# OnBoardOsc.net
KiCad netlist of a schematic drawn in Altium Designer
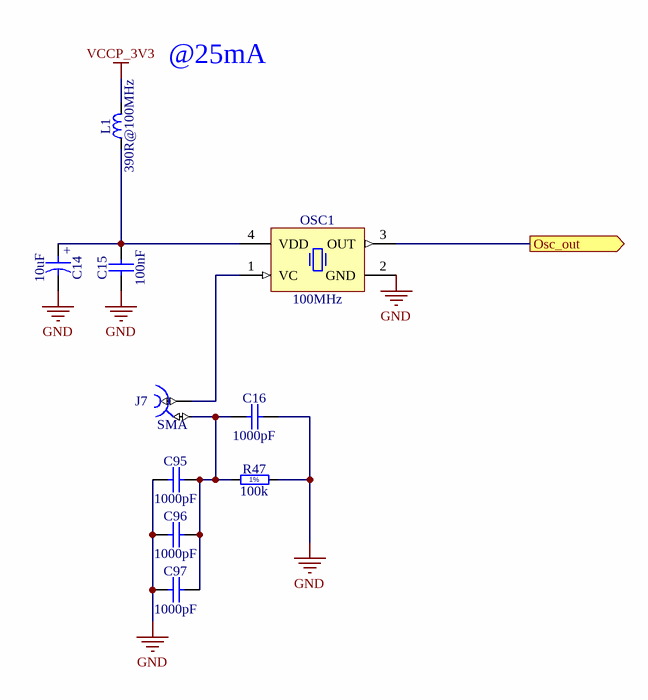
[diagram p0: OnBoardOsc.SchDoc]

(export (version "E")
  (design (tool "Eeschema 10.0.6"))
  (components
    (comp (ref "C14")
      (value "10uF")
      (footprint "CAPMP3216X180N")
      (description "Polarised capacitor")
      (fields
        (field (name "PART NUMBER") "CTE3216-18_10UF_10V_10%_LESR1800")
        (field (name "VOLTAGE") "10V")
        (field (name "AUTHOR") "CERN DEM JLC")
      )
      (libsource (lib "Capacitors") (part "Capacitor - polarized"))
    )
    (comp (ref "C15")
      (value "100nF")
      (footprint "CAPC1005X55N")
      (description "Non-polarised capacitor")
      (fields
        (field (name "PART NUMBER") "CC0402_100NF_16V_10%_X7R")
        (field (name "VOLTAGE") "16V")
        (field (name "AUTHOR") "CERN DEM JLC")
      )
      (libsource (lib "Capacitors") (part "Capacitor - non polarized"))
    )
    (comp (ref "C16")
      (value "1000pF")
      (footprint "CAPC1005X55N")
      (description "Non-polarised capacitor")
      (fields
        (field (name "PART NUMBER") "CC0402_1000PF_50V_5%_C0G")
        (field (name "VOLTAGE") "50V")
        (field (name "AUTHOR") "CERN DEM JLC")
      )
      (libsource (lib "Capacitors") (part "Capacitor - non polarized"))
    )
    (comp (ref "C95")
      (value "1000pF")
      (footprint "CAPC1005X55N")
      (description "Non-polarised capacitor")
      (fields
        (field (name "PART NUMBER") "CC0402_1000PF_50V_5%_C0G")
        (field (name "VOLTAGE") "50V")
        (field (name "AUTHOR") "CERN DEM JLC")
      )
      (libsource (lib "Capacitors") (part "Capacitor - non polarized"))
    )
    (comp (ref "C96")
      (value "1000pF")
      (footprint "CAPC1005X55N")
      (description "Non-polarised capacitor")
      (fields
        (field (name "PART NUMBER") "CC0402_1000PF_50V_5%_C0G")
        (field (name "VOLTAGE") "50V")
        (field (name "AUTHOR") "CERN DEM JLC")
      )
      (libsource (lib "Capacitors") (part "Capacitor - non polarized"))
    )
    (comp (ref "C97")
      (value "1000pF")
      (footprint "CAPC1005X55N")
      (description "Non-polarised capacitor")
      (fields
        (field (name "PART NUMBER") "CC0402_1000PF_50V_5%_C0G")
        (field (name "VOLTAGE") "50V")
        (field (name "AUTHOR") "CERN DEM JLC")
      )
      (libsource (lib "Capacitors") (part "Capacitor - non polarized"))
    )
    (comp (ref "J7")
      (value "SMA")
      (footprint "HUBER-SUHNER_82_SMA-50-0-41/133_NE")
      (fields
        (field (name "PART NUMBER") "HUBER-SUHNER_82_SMA-50-0-41/133_NE")
        (field (name "MANUFACTURER") "HUBER+SUHNER")
        (field (name "MANUFACTURER PART NUMBER") "82_SMA-50-0-41/133_NE")
        (field (name "AUTHOR") "CERN DEM JLC")
      )
      (libsource (lib "Connectors") (part "Coax_1Female_1Shield"))
    )
    (comp (ref "L1")
      (value "390R@100MHz")
      (footprint "INDC1608X95N")
      (description "Inductor")
      (fields
        (field (name "PART NUMBER") "IND0603_TDK_MPZ1608R391A")
        (field (name "POWER") "1.2A")
        (field (name "AUTHOR") "CERN DEM JLC")
      )
      (libsource (lib "Inductors & Transformers") (part "Inductor"))
    )
    (comp (ref "OSC1")
      (value "100MHz")
      (footprint "OSC_CRYSTEK_CVHD-950")
      (description "Oscillator 4 pins 1=VC 2=GND 3=OUT 4=VDD")
      (fields
        (field (name "PART NUMBER") "OSC_100MHZ_CRYSTEK_CVHD-950-100.000")
        (field (name "MANUFACTURER") "CRYSTEK CRYSTAL")
        (field (name "AUTHOR") "CERN DEM BC")
      )
      (libsource (lib "ICs And Semiconductors") (part "Oscillator 1VC 2GND 3OUT 4VDD"))
    )
    (comp (ref "R47")
      (value "100k")
      (footprint "RESC1005X40N")
      (description "Resistor - 1%")
      (fields
        (field (name "PART NUMBER") "R0402_100k_1%_0.0625W_100PPM")
        (field (name "POWER") "0.0625W")
        (field (name "AUTHOR") "CERN DEM JLC")
      )
      (libsource (lib "Resistors") (part "Resistor - 1%"))
    )
  )
  (nets
    (net (code "1") (name "/Osc_out") (class "Default")
      (node (ref "OSC1") (pin "3") (pinfunction "OUT_3") (pintype "output"))
    )
    (net (code "2") (name "GND") (class "Default")
      (node (ref "C14") (pin "2") (pinfunction "2_2") (pintype "passive"))
      (node (ref "C15") (pin "1") (pinfunction "1_1") (pintype "passive"))
      (node (ref "C16") (pin "2") (pinfunction "2_2") (pintype "passive"))
      (node (ref "C95") (pin "1") (pinfunction "1_1") (pintype "passive"))
      (node (ref "C96") (pin "1") (pinfunction "1_1") (pintype "passive"))
      (node (ref "C97") (pin "1") (pinfunction "1_1") (pintype "passive"))
      (node (ref "OSC1") (pin "2") (pinfunction "GND_2") (pintype "power_in"))
      (node (ref "R47") (pin "2") (pinfunction "2_2") (pintype "passive"))
    )
    (net (code "3") (name "Net-(C16-Pad1)") (class "Default")
      (node (ref "C16") (pin "1") (pinfunction "1_1") (pintype "passive"))
      (node (ref "C95") (pin "2") (pinfunction "2_2") (pintype "passive"))
      (node (ref "C96") (pin "2") (pinfunction "2_2") (pintype "passive"))
      (node (ref "C97") (pin "2") (pinfunction "2_2") (pintype "passive"))
      (node (ref "J7") (pin "2") (pinfunction "2_2") (pintype "bidirectional"))
      (node (ref "R47") (pin "1") (pinfunction "1_1") (pintype "passive"))
    )
    (net (code "4") (name "Net-(OSC1-VC)") (class "Default")
      (node (ref "J7") (pin "1") (pinfunction "1_1") (pintype "bidirectional"))
      (node (ref "OSC1") (pin "1") (pinfunction "VC_1") (pintype "input"))
    )
    (net (code "5") (name "Net-(OSC1-VDD)") (class "Default")
      (node (ref "C14") (pin "1") (pinfunction "1_1") (pintype "passive"))
      (node (ref "C15") (pin "2") (pinfunction "2_2") (pintype "passive"))
      (node (ref "L1") (pin "1") (pinfunction "1_1") (pintype "passive"))
      (node (ref "OSC1") (pin "4") (pinfunction "VDD_4") (pintype "power_in"))
    )
    (net (code "6") (name "VCCP_3V3") (class "Default")
      (node (ref "L1") (pin "2") (pinfunction "2_2") (pintype "passive"))
    )
  )
)
